# 2_MCU_Peripherals.net
KiCad netlist of a schematic drawn in Altium Designer
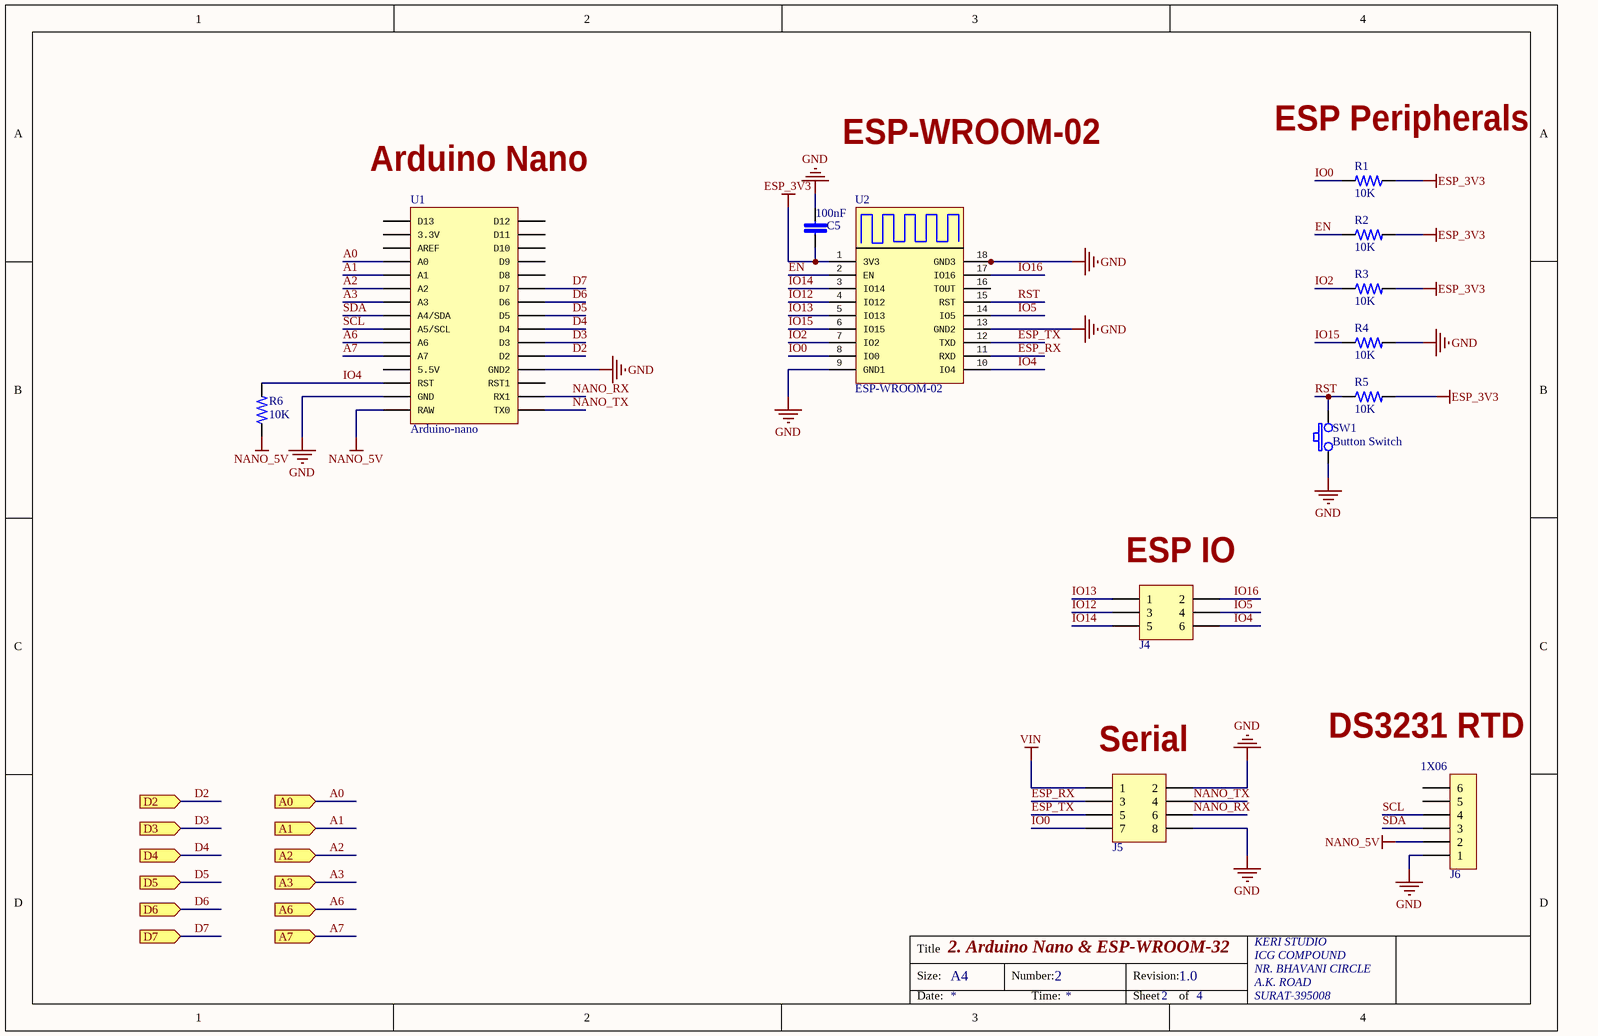
[diagram p0: 2. MCU & Peripherals.SchDoc]

(export (version "E")
  (design (tool "Eeschema 10.0.6"))
  (components
    (comp (ref "C5")
      (value "100nF")
      (footprint "C0805")
      (description "Multilayer Ceramic Capacitors MLCC - SMD/SMT 0805 0.1uF 50volts X7R 20%")
      (fields
        (field (name "MANUFACTURER") "Murata")
        (field (name "MANUFACTURER PART NUMBER") "GCJ21BR71H104MA01L")
      )
      (libsource (lib "keri_lib") (part "C_0805_0.1uF"))
    )
    (comp (ref "J4")
      (value "2X03")
      (footprint "Header_2.54mm_2X03")
      (description "Headers & Wire Housings 03+03 DIL VERTICAL PIN HEADER TIN")
      (fields (field (name "MANUFACTURER") "Harwin") (field (name "MANUFACTURER PART NUMBER") "M20-9980346"))
      (libsource (lib "keri_lib") (part "Header_2.54mm_2X03"))
    )
    (comp (ref "J5")
      (value "2X04")
      (footprint "Header_2.54mm_2X04")
      (description "Headers & Wire Housings 04+04 DIL VERTICAL PIN HEADER TIN")
      (fields (field (name "MANUFACTURER") "Harwin") (field (name "MANUFACTURER PART NUMBER") "M20-9980446"))
      (libsource (lib "keri_lib") (part "Header_2.54mm_2X04"))
    )
    (comp (ref "J6")
      (value "1X06")
      (footprint "Header_2.54mm_1X06")
      (description "CONNECTOR, 6WAY, VERTICAL, 2.54")
      (fields
        (field (name "MANUFACTURER") "TE Connectivity")
        (field (name "MANUFACTURER PART NUMBER") "826646-6")
      )
      (libsource (lib "keri_lib") (part "Header_2.54mm_1X06"))
    )
    (comp (ref "R1")
      (value "10K")
      (footprint "R0805")
      (description "Thick Film Resistors - SMD 10K 0805 5%")
      (fields (field (name "MANUFACTURER") "Bourns") (field (name "TOLERANCE") "5%"))
      (libsource (lib "keri_lib") (part "R_0805_10K"))
    )
    (comp (ref "R2")
      (value "10K")
      (footprint "R0805")
      (description "Thick Film Resistors - SMD 10K 0805 5%")
      (fields (field (name "MANUFACTURER") "Bourns") (field (name "TOLERANCE") "5%"))
      (libsource (lib "keri_lib") (part "R_0805_10K"))
    )
    (comp (ref "R3")
      (value "10K")
      (footprint "R0805")
      (description "Thick Film Resistors - SMD 10K 0805 5%")
      (fields (field (name "MANUFACTURER") "Bourns") (field (name "TOLERANCE") "5%"))
      (libsource (lib "keri_lib") (part "R_0805_10K"))
    )
    (comp (ref "R4")
      (value "10K")
      (footprint "R0805")
      (description "Thick Film Resistors - SMD 10K 0805 5%")
      (fields (field (name "MANUFACTURER") "Bourns") (field (name "TOLERANCE") "5%"))
      (libsource (lib "keri_lib") (part "R_0805_10K"))
    )
    (comp (ref "R5")
      (value "10K")
      (footprint "R0805")
      (description "Thick Film Resistors - SMD 10K 0805 5%")
      (fields (field (name "MANUFACTURER") "Bourns") (field (name "TOLERANCE") "5%"))
      (libsource (lib "keri_lib") (part "R_0805_10K"))
    )
    (comp (ref "R6")
      (value "10K")
      (footprint "R0805")
      (description "Thick Film Resistors - SMD 10K 0805 5%")
      (fields (field (name "MANUFACTURER") "Bourns") (field (name "TOLERANCE") "5%"))
      (libsource (lib "keri_lib") (part "R_0805_10K"))
    )
    (comp (ref "SW1")
      (value "Button Switch")
      (footprint "KSR231GLFS")
      (description "SWITCH TACTILE SPST-NO 0.05A 32V")
      (fields (field (name "MANUFACTURER") "ITT C&K") (field (name "MANUFACTURER PART NUMBER") "KSR231GLFS"))
      (libsource (lib "keri_lib") (part "Button_Switch"))
    )
    (comp (ref "U1")
      (value "Arduino-nano")
      (footprint "ARDUINO_NANO")
      (description "ARDUINO   A000005   ATMEGA328, ARDUINO NANO, EVAL BOARD")
      (fields (field (name "MANUFACTURER") "Arduino") (field (name "MANUFACTURER PART NUMBER") "A000005"))
      (libsource (lib "keri_lib") (part "Arduino-nano"))
    )
    (comp (ref "U2")
      (value "ESP-WROOM-02")
      (footprint "ESP-WROOM-02")
      (description "WiFi Modules (802.11) SMD Module, ESP8266EX, 16Mbits SPI flash, UART Mode")
      (fields (field (name "MANUFACTURER") "Espressif Systems"))
      (libsource (lib "keri_lib") (part "ESP-WROOM-02"))
    )
  )
  (nets
    (net (code "1") (name "/A0") (class "Default")
      (node (ref "U1") (pin "A0") (pinfunction "A0_A0") (pintype "passive"))
    )
    (net (code "2") (name "/A1") (class "Default")
      (node (ref "U1") (pin "A1") (pinfunction "A1_A1") (pintype "passive"))
    )
    (net (code "3") (name "/A2") (class "Default")
      (node (ref "U1") (pin "A2") (pinfunction "A2_A2") (pintype "passive"))
    )
    (net (code "4") (name "/A3") (class "Default")
      (node (ref "U1") (pin "A3") (pinfunction "A3_A3") (pintype "passive"))
    )
    (net (code "5") (name "/A6") (class "Default")
      (node (ref "U1") (pin "A6") (pinfunction "A6_A6") (pintype "passive"))
    )
    (net (code "6") (name "/A7") (class "Default")
      (node (ref "U1") (pin "A7") (pinfunction "A7_A7") (pintype "passive"))
    )
    (net (code "7") (name "/D2") (class "Default")
      (node (ref "U1") (pin "D2") (pinfunction "D2_D2") (pintype "passive"))
    )
    (net (code "8") (name "/D3") (class "Default")
      (node (ref "U1") (pin "D3") (pinfunction "D3_D3") (pintype "passive"))
    )
    (net (code "9") (name "/D4") (class "Default")
      (node (ref "U1") (pin "D4") (pinfunction "D4_D4") (pintype "passive"))
    )
    (net (code "10") (name "/D5") (class "Default")
      (node (ref "U1") (pin "D5") (pinfunction "D5_D5") (pintype "passive"))
    )
    (net (code "11") (name "/D6") (class "Default")
      (node (ref "U1") (pin "D6") (pinfunction "D6_D6") (pintype "passive"))
    )
    (net (code "12") (name "/D7") (class "Default")
      (node (ref "U1") (pin "D7") (pinfunction "D7_D7") (pintype "passive"))
    )
    (net (code "13") (name "/EN") (class "Default")
      (node (ref "R2") (pin "1") (pinfunction "1_1") (pintype "passive"))
      (node (ref "U2") (pin "2") (pinfunction "EN_2") (pintype "passive"))
    )
    (net (code "14") (name "/ESP_RX") (class "Default")
      (node (ref "J5") (pin "3") (pinfunction "3_3") (pintype "passive"))
      (node (ref "U2") (pin "11") (pinfunction "RXD_11") (pintype "passive"))
    )
    (net (code "15") (name "/ESP_TX") (class "Default")
      (node (ref "J5") (pin "5") (pinfunction "5_5") (pintype "passive"))
      (node (ref "U2") (pin "12") (pinfunction "TXD_12") (pintype "passive"))
    )
    (net (code "16") (name "/IO0") (class "Default")
      (node (ref "J5") (pin "7") (pinfunction "7_7") (pintype "passive"))
      (node (ref "R1") (pin "2") (pinfunction "2_2") (pintype "passive"))
      (node (ref "U2") (pin "8") (pinfunction "IO0_8") (pintype "passive"))
    )
    (net (code "17") (name "/IO2") (class "Default")
      (node (ref "R3") (pin "1") (pinfunction "1_1") (pintype "passive"))
      (node (ref "U2") (pin "7") (pinfunction "IO2_7") (pintype "passive"))
    )
    (net (code "18") (name "/IO4") (class "Default")
      (node (ref "J4") (pin "6") (pinfunction "6_6") (pintype "passive"))
      (node (ref "R6") (pin "2") (pinfunction "2_2") (pintype "passive"))
      (node (ref "U1") (pin "RST") (pinfunction "RST_RST") (pintype "passive"))
      (node (ref "U2") (pin "10") (pinfunction "IO4_10") (pintype "passive"))
    )
    (net (code "19") (name "/IO5") (class "Default")
      (node (ref "J4") (pin "4") (pinfunction "4_4") (pintype "passive"))
      (node (ref "U2") (pin "14") (pinfunction "IO5_14") (pintype "open_collector"))
    )
    (net (code "20") (name "/IO12") (class "Default")
      (node (ref "J4") (pin "3") (pinfunction "3_3") (pintype "passive"))
      (node (ref "U2") (pin "4") (pinfunction "IO12_4") (pintype "passive"))
    )
    (net (code "21") (name "/IO13") (class "Default")
      (node (ref "J4") (pin "1") (pinfunction "1_1") (pintype "passive"))
      (node (ref "U2") (pin "5") (pinfunction "IO13_5") (pintype "passive"))
    )
    (net (code "22") (name "/IO14") (class "Default")
      (node (ref "J4") (pin "5") (pinfunction "5_5") (pintype "passive"))
      (node (ref "U2") (pin "3") (pinfunction "IO14_3") (pintype "passive"))
    )
    (net (code "23") (name "/IO15") (class "Default")
      (node (ref "R4") (pin "1") (pinfunction "1_1") (pintype "passive"))
      (node (ref "U2") (pin "6") (pinfunction "IO15_6") (pintype "passive"))
    )
    (net (code "24") (name "/IO16") (class "Default")
      (node (ref "J4") (pin "2") (pinfunction "2_2") (pintype "passive"))
      (node (ref "U2") (pin "17") (pinfunction "IO16_17") (pintype "passive"))
    )
    (net (code "25") (name "/NANO_RX") (class "Default")
      (node (ref "J5") (pin "6") (pinfunction "6_6") (pintype "passive"))
      (node (ref "U1") (pin "RX1") (pinfunction "RX1_RX1") (pintype "passive"))
    )
    (net (code "26") (name "/NANO_TX") (class "Default")
      (node (ref "J5") (pin "4") (pinfunction "4_4") (pintype "passive"))
      (node (ref "U1") (pin "TX0") (pinfunction "TX0_TX0") (pintype "passive"))
    )
    (net (code "27") (name "/RST") (class "Default")
      (node (ref "R5") (pin "1") (pinfunction "1_1") (pintype "passive"))
      (node (ref "SW1") (pin "2") (pintype "passive"))
      (node (ref "U2") (pin "15") (pinfunction "RST_15") (pintype "passive"))
    )
    (net (code "28") (name "/SCL") (class "Default")
      (node (ref "J6") (pin "4") (pinfunction "4_4") (pintype "passive"))
      (node (ref "U1") (pin "A5") (pinfunction "A5/SCL_A5") (pintype "passive"))
    )
    (net (code "29") (name "/SDA") (class "Default")
      (node (ref "J6") (pin "3") (pinfunction "3_3") (pintype "passive"))
      (node (ref "U1") (pin "A4") (pinfunction "A4/SDA_A4") (pintype "passive"))
    )
    (net (code "30") (name "ESP_3V3") (class "Default")
      (node (ref "C5") (pin "2") (pinfunction "2_2") (pintype "passive"))
      (node (ref "R1") (pin "1") (pinfunction "1_1") (pintype "passive"))
      (node (ref "R2") (pin "2") (pinfunction "2_2") (pintype "passive"))
      (node (ref "R3") (pin "2") (pinfunction "2_2") (pintype "passive"))
      (node (ref "R5") (pin "2") (pinfunction "2_2") (pintype "passive"))
      (node (ref "U2") (pin "1") (pinfunction "3V3_1") (pintype "power_in"))
    )
    (net (code "31") (name "GND") (class "Default")
      (node (ref "C5") (pin "1") (pinfunction "1_1") (pintype "passive"))
      (node (ref "J5") (pin "2") (pinfunction "2_2") (pintype "passive"))
      (node (ref "J5") (pin "8") (pinfunction "8_8") (pintype "passive"))
      (node (ref "J6") (pin "1") (pinfunction "1_1") (pintype "passive"))
      (node (ref "R4") (pin "2") (pinfunction "2_2") (pintype "passive"))
      (node (ref "SW1") (pin "1") (pintype "passive"))
      (node (ref "U1") (pin "GND") (pinfunction "GND_GND") (pintype "passive"))
      (node (ref "U1") (pin "GND1") (pinfunction "GND2_GND1") (pintype "passive"))
      (node (ref "U2") (pin "13") (pinfunction "GND2_13") (pintype "power_in"))
      (node (ref "U2") (pin "18") (pinfunction "GND3_18") (pintype "power_in"))
      (node (ref "U2") (pin "19") (pinfunction "GND0_19") (pintype "power_in"))
      (node (ref "U2") (pin "9") (pinfunction "GND1_9") (pintype "power_in"))
    )
    (net (code "32") (name "NANO_5V") (class "Default")
      (node (ref "J6") (pin "2") (pinfunction "2_2") (pintype "passive"))
      (node (ref "R6") (pin "1") (pinfunction "1_1") (pintype "passive"))
      (node (ref "U1") (pin "RAW") (pinfunction "RAW_RAW") (pintype "passive"))
    )
    (net (code "33") (name "VIN") (class "Default")
      (node (ref "J5") (pin "1") (pinfunction "1_1") (pintype "passive"))
    )
    (net (code "34") (name "unconnected-(J6-Pad5)") (class "Default")
      (node (ref "J6") (pin "5") (pinfunction "5_5") (pintype "passive"))
    )
    (net (code "35") (name "unconnected-(J6-Pad6)") (class "Default")
      (node (ref "J6") (pin "6") (pinfunction "6_6") (pintype "passive"))
    )
    (net (code "36") (name "unconnected-(U1-5.5V-Pad5V)") (class "Default")
      (node (ref "U1") (pin "5V") (pinfunction "5.5V_5V") (pintype "passive"))
    )
    (net (code "37") (name "unconnected-(U1-Pad3.3V)") (class "Default")
      (node (ref "U1") (pin "3.3V") (pinfunction "3.3V_3.3V") (pintype "passive"))
    )
    (net (code "38") (name "unconnected-(U1-PadAREF)") (class "Default")
      (node (ref "U1") (pin "AREF") (pinfunction "AREF_AREF") (pintype "passive"))
    )
    (net (code "39") (name "unconnected-(U1-PadD8)") (class "Default")
      (node (ref "U1") (pin "D8") (pinfunction "D8_D8") (pintype "passive"))
    )
    (net (code "40") (name "unconnected-(U1-PadD9)") (class "Default")
      (node (ref "U1") (pin "D9") (pinfunction "D9_D9") (pintype "passive"))
    )
    (net (code "41") (name "unconnected-(U1-PadD10)") (class "Default")
      (node (ref "U1") (pin "D10") (pinfunction "D10_D10") (pintype "passive"))
    )
    (net (code "42") (name "unconnected-(U1-PadD11)") (class "Default")
      (node (ref "U1") (pin "D11") (pinfunction "D11_D11") (pintype "passive"))
    )
    (net (code "43") (name "unconnected-(U1-PadD12)") (class "Default")
      (node (ref "U1") (pin "D12") (pinfunction "D12_D12") (pintype "passive"))
    )
    (net (code "44") (name "unconnected-(U1-PadD13)") (class "Default")
      (node (ref "U1") (pin "D13") (pinfunction "D13_D13") (pintype "passive"))
    )
    (net (code "45") (name "unconnected-(U1-PadRST1)") (class "Default")
      (node (ref "U1") (pin "RST1") (pinfunction "RST1_RST1") (pintype "passive"))
    )
    (net (code "46") (name "unconnected-(U2-TOUT-Pad16)") (class "Default")
      (node (ref "U2") (pin "16") (pinfunction "TOUT_16") (pintype "passive"))
    )
  )
)
